# LPCB235_-_PUSHER_INTERLOCK.net
KiCad netlist of a schematic drawn in Altium Designer
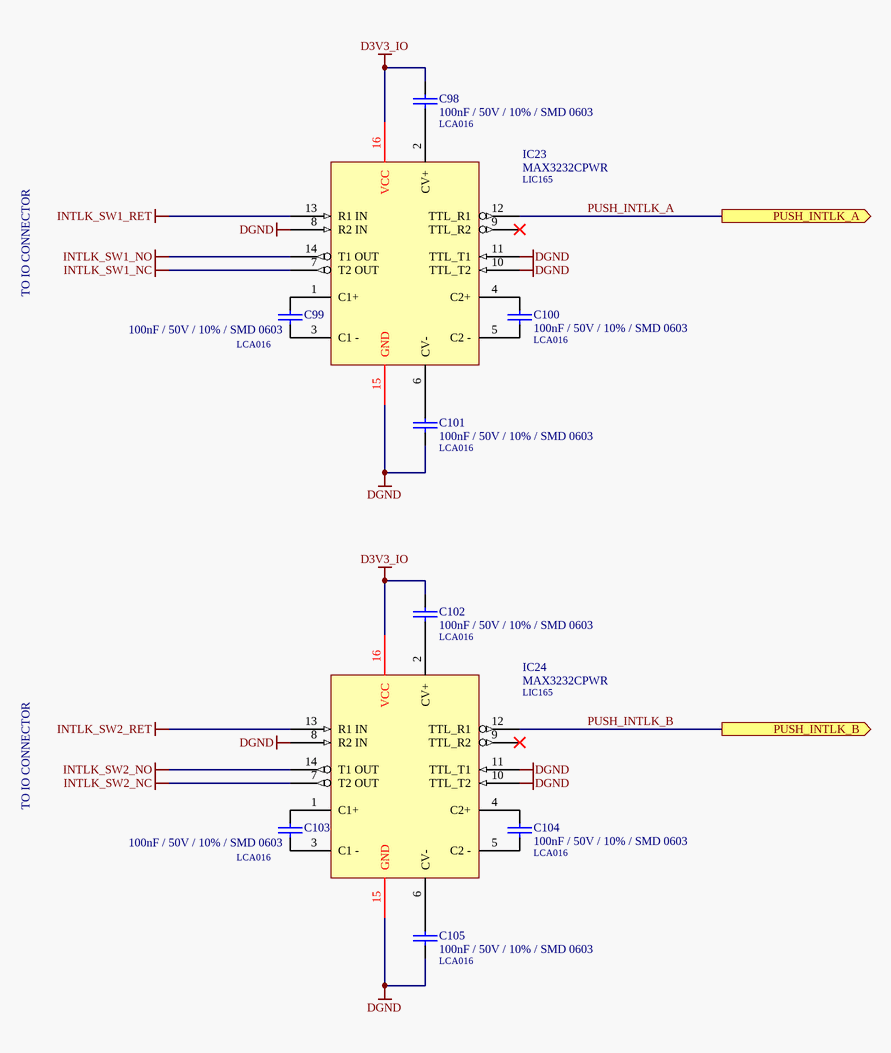
[diagram p0: LPCB235 - PUSHER INTERLOCK.SchDoc]

(export (version "E")
  (design (tool "Eeschema 10.0.6"))
  (components
    (comp (ref "C98")
      (value "100nF / 50V / 10% / SMD 0603")
      (footprint "LFP011__CC1608-0603-IPC7351_B")
      (description "Capacitor, Ceramic Chip, 100nF (0.1uF), 50V, 5%, SMD 0603 [LCA016]")
      (fields (field (name "LDL_NUMBER") "LCA016"))
      (libsource (lib "LDL_Capacitors") (part "100nF / 50V / 10% / SMD 0603"))
    )
    (comp (ref "C99")
      (value "100nF / 50V / 10% / SMD 0603")
      (footprint "LFP011__CC1608-0603-IPC7351_B")
      (description "Capacitor, Ceramic Chip, 100nF (0.1uF), 50V, 5%, SMD 0603 [LCA016]")
      (fields (field (name "LDL_NUMBER") "LCA016"))
      (libsource (lib "LDL_Capacitors") (part "100nF / 50V / 10% / SMD 0603"))
    )
    (comp (ref "C100")
      (value "100nF / 50V / 10% / SMD 0603")
      (footprint "LFP011__CC1608-0603-IPC7351_B")
      (description "Capacitor, Ceramic Chip, 100nF (0.1uF), 50V, 5%, SMD 0603 [LCA016]")
      (fields (field (name "LDL_NUMBER") "LCA016"))
      (libsource (lib "LDL_Capacitors") (part "100nF / 50V / 10% / SMD 0603"))
    )
    (comp (ref "C101")
      (value "100nF / 50V / 10% / SMD 0603")
      (footprint "LFP011__CC1608-0603-IPC7351_B")
      (description "Capacitor, Ceramic Chip, 100nF (0.1uF), 50V, 5%, SMD 0603 [LCA016]")
      (fields (field (name "LDL_NUMBER") "LCA016"))
      (libsource (lib "LDL_Capacitors") (part "100nF / 50V / 10% / SMD 0603"))
    )
    (comp (ref "C102")
      (value "100nF / 50V / 10% / SMD 0603")
      (footprint "LFP011__CC1608-0603-IPC7351_B")
      (description "Capacitor, Ceramic Chip, 100nF (0.1uF), 50V, 5%, SMD 0603 [LCA016]")
      (fields (field (name "LDL_NUMBER") "LCA016"))
      (libsource (lib "LDL_Capacitors") (part "100nF / 50V / 10% / SMD 0603"))
    )
    (comp (ref "C103")
      (value "100nF / 50V / 10% / SMD 0603")
      (footprint "LFP011__CC1608-0603-IPC7351_B")
      (description "Capacitor, Ceramic Chip, 100nF (0.1uF), 50V, 5%, SMD 0603 [LCA016]")
      (fields (field (name "LDL_NUMBER") "LCA016"))
      (libsource (lib "LDL_Capacitors") (part "100nF / 50V / 10% / SMD 0603"))
    )
    (comp (ref "C104")
      (value "100nF / 50V / 10% / SMD 0603")
      (footprint "LFP011__CC1608-0603-IPC7351_B")
      (description "Capacitor, Ceramic Chip, 100nF (0.1uF), 50V, 5%, SMD 0603 [LCA016]")
      (fields (field (name "LDL_NUMBER") "LCA016"))
      (libsource (lib "LDL_Capacitors") (part "100nF / 50V / 10% / SMD 0603"))
    )
    (comp (ref "C105")
      (value "100nF / 50V / 10% / SMD 0603")
      (footprint "LFP011__CC1608-0603-IPC7351_B")
      (description "Capacitor, Ceramic Chip, 100nF (0.1uF), 50V, 5%, SMD 0603 [LCA016]")
      (fields (field (name "LDL_NUMBER") "LCA016"))
      (libsource (lib "LDL_Capacitors") (part "100nF / 50V / 10% / SMD 0603"))
    )
    (comp (ref "IC23")
      (value "MAX3232CPWR")
      (footprint "LFP049__TSSOP-16")
      (description "IC, RS232 Line Driver, 3.3V, SMD TSSOP16 [LIC165]")
      (fields (field (name "LDL_NUMBER") "LIC165"))
      (libsource (lib "LDL_Semiconductors") (part "MAX3232CPWR"))
    )
    (comp (ref "IC24")
      (value "MAX3232CPWR")
      (footprint "LFP049__TSSOP-16")
      (description "IC, RS232 Line Driver, 3.3V, SMD TSSOP16 [LIC165]")
      (fields (field (name "LDL_NUMBER") "LIC165"))
      (libsource (lib "LDL_Semiconductors") (part "MAX3232CPWR"))
    )
  )
  (nets
    (net (code "1") (name "/PUSH_INTLK_A") (class "Default")
      (node (ref "IC23") (pin "12") (pinfunction "TTL_R1_12") (pintype "output"))
    )
    (net (code "2") (name "/PUSH_INTLK_B") (class "Default")
      (node (ref "IC24") (pin "12") (pinfunction "TTL_R1_12") (pintype "output"))
    )
    (net (code "3") (name "D3V3_IO") (class "Default")
      (node (ref "C102") (pin "1") (pintype "passive"))
      (node (ref "C98") (pin "1") (pintype "passive"))
      (node (ref "IC23") (pin "16") (pinfunction "VCC_16") (pintype "power_in"))
      (node (ref "IC24") (pin "16") (pinfunction "VCC_16") (pintype "power_in"))
    )
    (net (code "4") (name "DGND") (class "Default")
      (node (ref "C101") (pin "2") (pintype "passive"))
      (node (ref "C105") (pin "2") (pintype "passive"))
      (node (ref "IC23") (pin "10") (pinfunction "TTL_T2_10") (pintype "input"))
      (node (ref "IC23") (pin "11") (pinfunction "TTL_T1_11") (pintype "input"))
      (node (ref "IC23") (pin "15") (pinfunction "GND_15") (pintype "power_in"))
      (node (ref "IC23") (pin "8") (pinfunction "R2_IN_8") (pintype "input"))
      (node (ref "IC24") (pin "10") (pinfunction "TTL_T2_10") (pintype "input"))
      (node (ref "IC24") (pin "11") (pinfunction "TTL_T1_11") (pintype "input"))
      (node (ref "IC24") (pin "15") (pinfunction "GND_15") (pintype "power_in"))
      (node (ref "IC24") (pin "8") (pinfunction "R2_IN_8") (pintype "input"))
    )
    (net (code "5") (name "INTLK_SW1_NC") (class "Default")
      (node (ref "IC23") (pin "7") (pinfunction "T2_OUT_7") (pintype "output"))
    )
    (net (code "6") (name "INTLK_SW1_NO") (class "Default")
      (node (ref "IC23") (pin "14") (pinfunction "T1_OUT_14") (pintype "output"))
    )
    (net (code "7") (name "INTLK_SW1_RET") (class "Default")
      (node (ref "IC23") (pin "13") (pinfunction "R1_IN_13") (pintype "input"))
    )
    (net (code "8") (name "INTLK_SW2_NC") (class "Default")
      (node (ref "IC24") (pin "7") (pinfunction "T2_OUT_7") (pintype "output"))
    )
    (net (code "9") (name "INTLK_SW2_NO") (class "Default")
      (node (ref "IC24") (pin "14") (pinfunction "T1_OUT_14") (pintype "output"))
    )
    (net (code "10") (name "INTLK_SW2_RET") (class "Default")
      (node (ref "IC24") (pin "13") (pinfunction "R1_IN_13") (pintype "input"))
    )
    (net (code "11") (name "Net-(IC23-C1+)") (class "Default")
      (node (ref "C99") (pin "1") (pintype "passive"))
      (node (ref "IC23") (pin "1") (pinfunction "C1+_1") (pintype "passive"))
    )
    (net (code "12") (name "Net-(IC23-C1_-)") (class "Default")
      (node (ref "C99") (pin "2") (pintype "passive"))
      (node (ref "IC23") (pin "3") (pinfunction "C1_-_3") (pintype "passive"))
    )
    (net (code "13") (name "Net-(IC23-C2+)") (class "Default")
      (node (ref "C100") (pin "1") (pintype "passive"))
      (node (ref "IC23") (pin "4") (pinfunction "C2+_4") (pintype "passive"))
    )
    (net (code "14") (name "Net-(IC23-C2_-)") (class "Default")
      (node (ref "C100") (pin "2") (pintype "passive"))
      (node (ref "IC23") (pin "5") (pinfunction "C2_-_5") (pintype "passive"))
    )
    (net (code "15") (name "Net-(IC23-CV+)") (class "Default")
      (node (ref "C98") (pin "2") (pintype "passive"))
      (node (ref "IC23") (pin "2") (pinfunction "CV+_2") (pintype "passive"))
    )
    (net (code "16") (name "Net-(IC23-CV-)") (class "Default")
      (node (ref "C101") (pin "1") (pintype "passive"))
      (node (ref "IC23") (pin "6") (pinfunction "CV-_6") (pintype "passive"))
    )
    (net (code "17") (name "Net-(IC24-C1+)") (class "Default")
      (node (ref "C103") (pin "1") (pintype "passive"))
      (node (ref "IC24") (pin "1") (pinfunction "C1+_1") (pintype "passive"))
    )
    (net (code "18") (name "Net-(IC24-C1_-)") (class "Default")
      (node (ref "C103") (pin "2") (pintype "passive"))
      (node (ref "IC24") (pin "3") (pinfunction "C1_-_3") (pintype "passive"))
    )
    (net (code "19") (name "Net-(IC24-C2+)") (class "Default")
      (node (ref "C104") (pin "1") (pintype "passive"))
      (node (ref "IC24") (pin "4") (pinfunction "C2+_4") (pintype "passive"))
    )
    (net (code "20") (name "Net-(IC24-C2_-)") (class "Default")
      (node (ref "C104") (pin "2") (pintype "passive"))
      (node (ref "IC24") (pin "5") (pinfunction "C2_-_5") (pintype "passive"))
    )
    (net (code "21") (name "Net-(IC24-CV+)") (class "Default")
      (node (ref "C102") (pin "2") (pintype "passive"))
      (node (ref "IC24") (pin "2") (pinfunction "CV+_2") (pintype "passive"))
    )
    (net (code "22") (name "Net-(IC24-CV-)") (class "Default")
      (node (ref "C105") (pin "1") (pintype "passive"))
      (node (ref "IC24") (pin "6") (pinfunction "CV-_6") (pintype "passive"))
    )
    (net (code "23") (name "unconnected-(IC23-TTL_R2-Pad9)") (class "Default")
      (node (ref "IC23") (pin "9") (pinfunction "TTL_R2_9") (pintype "output+no_connect"))
    )
    (net (code "24") (name "unconnected-(IC24-TTL_R2-Pad9)") (class "Default")
      (node (ref "IC24") (pin "9") (pinfunction "TTL_R2_9") (pintype "output+no_connect"))
    )
  )
)
